# PidiPC.net
KiCad netlist of a schematic drawn in EAGLE
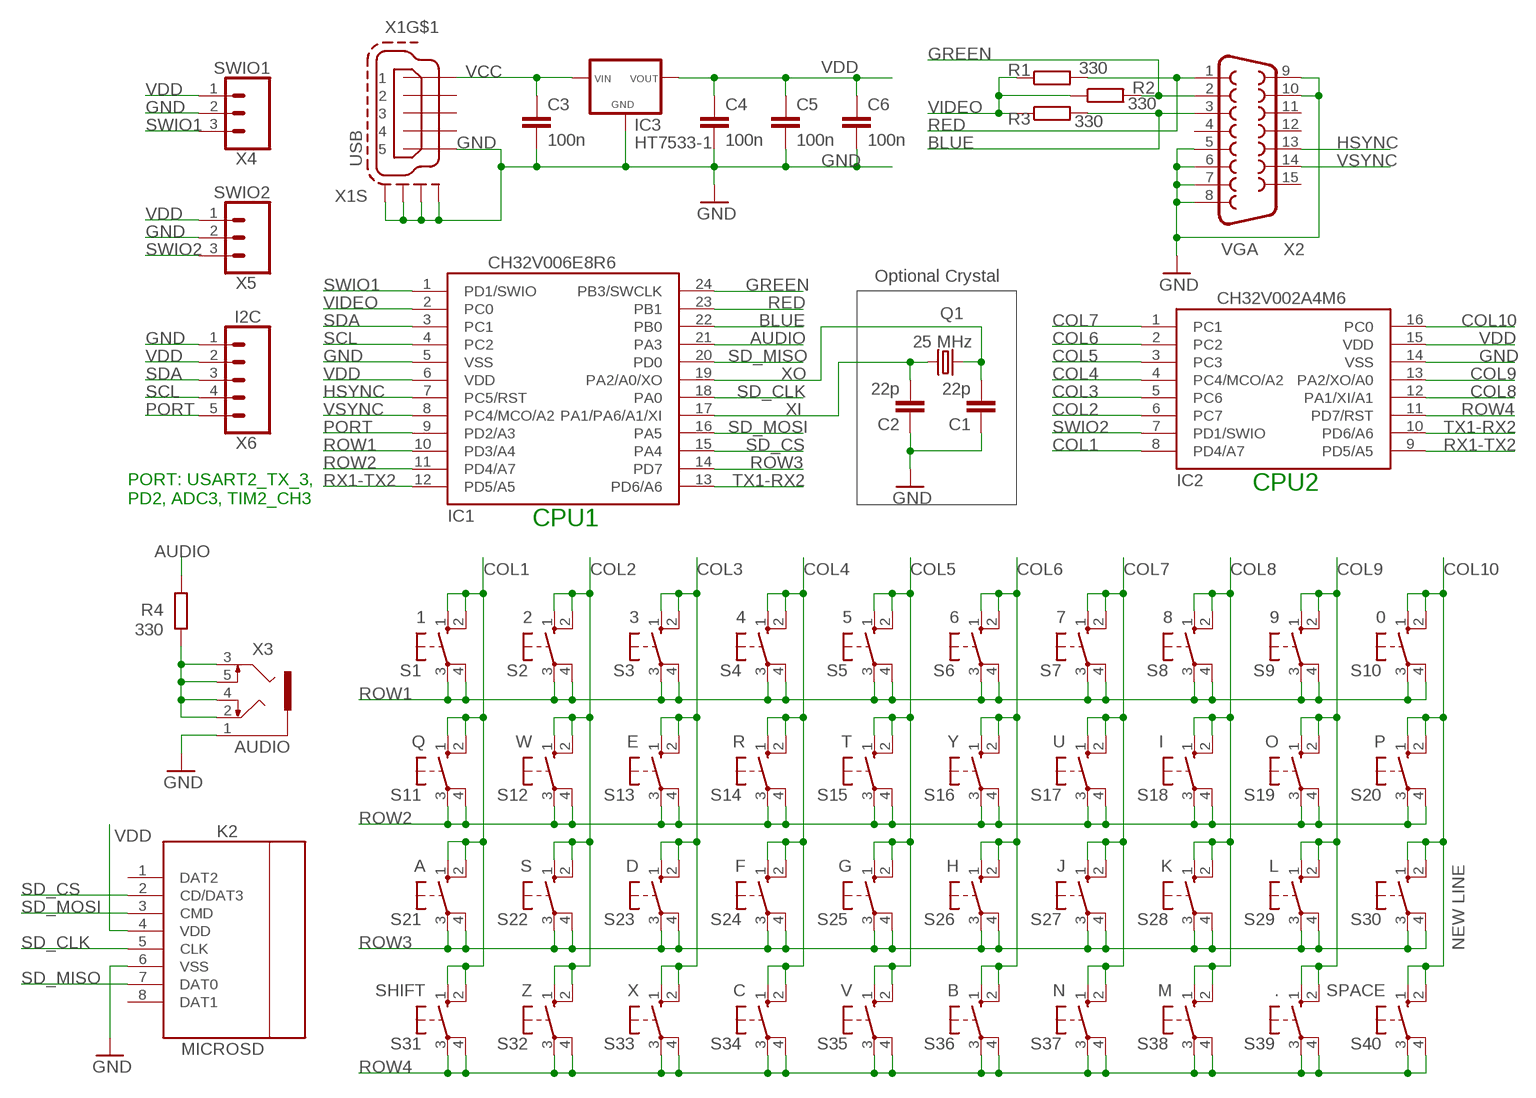
[diagram p0: schematic, sheet 1]

(export (version "E")
  (design (tool "Eeschema 10.0.6"))
  (components
    (comp (ref "C1")
      (value "22p")
      (footprint "eagle-import:C050-024X044")
      (libsource (lib "eagle-import") (part "C-EU050-024X044"))
    )
    (comp (ref "C2")
      (value "22p")
      (footprint "eagle-import:C050-024X044")
      (libsource (lib "eagle-import") (part "C-EU050-024X044"))
    )
    (comp (ref "C3")
      (value "100n")
      (footprint "eagle-import:C050-024X044")
      (libsource (lib "eagle-import") (part "C-EU050-024X044"))
    )
    (comp (ref "C4")
      (value "100n")
      (footprint "eagle-import:C050-024X044")
      (libsource (lib "eagle-import") (part "C-EU050-024X044"))
    )
    (comp (ref "C5")
      (value "100n")
      (footprint "eagle-import:C050-024X044")
      (libsource (lib "eagle-import") (part "C-EU050-024X044"))
    )
    (comp (ref "C6")
      (value "100n")
      (footprint "eagle-import:C050-024X044")
      (libsource (lib "eagle-import") (part "C-EU050-024X044"))
    )
    (comp (ref "IC1")
      (value "CH32V006E8R6")
      (footprint "eagle-import:QSOP24")
      (libsource (lib "eagle-import") (part "CH32V006E8R6"))
    )
    (comp (ref "IC2")
      (value "CH32V002A4M6")
      (footprint "eagle-import:SOP16")
      (libsource (lib "eagle-import") (part "CH32V002A4M6"))
    )
    (comp (ref "IC3")
      (value "HT7533-1")
      (footprint "eagle-import:HT7533-1")
      (libsource (lib "eagle-import") (part "HT7533-1"))
    )
    (comp (ref "K2")
      (value "MICROSD")
      (footprint "eagle-import:MICROSD")
      (libsource (lib "eagle-import") (part "MICROSD"))
    )
    (comp (ref "Q1")
      (value "25 MHz")
      (footprint "eagle-import:HC49U-V")
      (libsource (lib "eagle-import") (part "CRYSTALHC49U-V"))
    )
    (comp (ref "R1")
      (value "330")
      (footprint "eagle-import:0204_7")
      (libsource (lib "eagle-import") (part "R-EU_0204/7"))
    )
    (comp (ref "R2")
      (value "330")
      (footprint "eagle-import:0204_7")
      (libsource (lib "eagle-import") (part "R-EU_0204/7"))
    )
    (comp (ref "R3")
      (value "330")
      (footprint "eagle-import:0204_7")
      (libsource (lib "eagle-import") (part "R-EU_0204/7"))
    )
    (comp (ref "R4")
      (value "330")
      (footprint "eagle-import:0204_7")
      (libsource (lib "eagle-import") (part "R-EU_0204/7"))
    )
    (comp (ref "S1")
      (value "1")
      (footprint "eagle-import:B3F-10XX")
      (fields (field (name "MPN") "B3F-1000"))
      (libsource (lib "eagle-import") (part "10-XX"))
    )
    (comp (ref "S2")
      (value "2")
      (footprint "eagle-import:B3F-10XX")
      (fields (field (name "MPN") "B3F-1000"))
      (libsource (lib "eagle-import") (part "10-XX"))
    )
    (comp (ref "S3")
      (value "3")
      (footprint "eagle-import:B3F-10XX")
      (fields (field (name "MPN") "B3F-1000"))
      (libsource (lib "eagle-import") (part "10-XX"))
    )
    (comp (ref "S4")
      (value "4")
      (footprint "eagle-import:B3F-10XX")
      (fields (field (name "MPN") "B3F-1000"))
      (libsource (lib "eagle-import") (part "10-XX"))
    )
    (comp (ref "S5")
      (value "5")
      (footprint "eagle-import:B3F-10XX")
      (fields (field (name "MPN") "B3F-1000"))
      (libsource (lib "eagle-import") (part "10-XX"))
    )
    (comp (ref "S6")
      (value "6")
      (footprint "eagle-import:B3F-10XX")
      (fields (field (name "MPN") "B3F-1000"))
      (libsource (lib "eagle-import") (part "10-XX"))
    )
    (comp (ref "S7")
      (value "7")
      (footprint "eagle-import:B3F-10XX")
      (fields (field (name "MPN") "B3F-1000"))
      (libsource (lib "eagle-import") (part "10-XX"))
    )
    (comp (ref "S8")
      (value "8")
      (footprint "eagle-import:B3F-10XX")
      (fields (field (name "MPN") "B3F-1000"))
      (libsource (lib "eagle-import") (part "10-XX"))
    )
    (comp (ref "S9")
      (value "9")
      (footprint "eagle-import:B3F-10XX")
      (fields (field (name "MPN") "B3F-1000"))
      (libsource (lib "eagle-import") (part "10-XX"))
    )
    (comp (ref "S10")
      (value "0")
      (footprint "eagle-import:B3F-10XX")
      (fields (field (name "MPN") "B3F-1000"))
      (libsource (lib "eagle-import") (part "10-XX"))
    )
    (comp (ref "S11")
      (value "Q")
      (footprint "eagle-import:B3F-10XX")
      (fields (field (name "MPN") "B3F-1000"))
      (libsource (lib "eagle-import") (part "10-XX"))
    )
    (comp (ref "S12")
      (value "W")
      (footprint "eagle-import:B3F-10XX")
      (fields (field (name "MPN") "B3F-1000"))
      (libsource (lib "eagle-import") (part "10-XX"))
    )
    (comp (ref "S13")
      (value "E")
      (footprint "eagle-import:B3F-10XX")
      (fields (field (name "MPN") "B3F-1000"))
      (libsource (lib "eagle-import") (part "10-XX"))
    )
    (comp (ref "S14")
      (value "R")
      (footprint "eagle-import:B3F-10XX")
      (fields (field (name "MPN") "B3F-1000"))
      (libsource (lib "eagle-import") (part "10-XX"))
    )
    (comp (ref "S15")
      (value "T")
      (footprint "eagle-import:B3F-10XX")
      (fields (field (name "MPN") "B3F-1000"))
      (libsource (lib "eagle-import") (part "10-XX"))
    )
    (comp (ref "S16")
      (value "Y")
      (footprint "eagle-import:B3F-10XX")
      (fields (field (name "MPN") "B3F-1000"))
      (libsource (lib "eagle-import") (part "10-XX"))
    )
    (comp (ref "S17")
      (value "U")
      (footprint "eagle-import:B3F-10XX")
      (fields (field (name "MPN") "B3F-1000"))
      (libsource (lib "eagle-import") (part "10-XX"))
    )
    (comp (ref "S18")
      (value "I")
      (footprint "eagle-import:B3F-10XX")
      (fields (field (name "MPN") "B3F-1000"))
      (libsource (lib "eagle-import") (part "10-XX"))
    )
    (comp (ref "S19")
      (value "O")
      (footprint "eagle-import:B3F-10XX")
      (fields (field (name "MPN") "B3F-1000"))
      (libsource (lib "eagle-import") (part "10-XX"))
    )
    (comp (ref "S20")
      (value "P")
      (footprint "eagle-import:B3F-10XX")
      (fields (field (name "MPN") "B3F-1000"))
      (libsource (lib "eagle-import") (part "10-XX"))
    )
    (comp (ref "S21")
      (value "A")
      (footprint "eagle-import:B3F-10XX")
      (fields (field (name "MPN") "B3F-1000"))
      (libsource (lib "eagle-import") (part "10-XX"))
    )
    (comp (ref "S22")
      (value "S")
      (footprint "eagle-import:B3F-10XX")
      (fields (field (name "MPN") "B3F-1000"))
      (libsource (lib "eagle-import") (part "10-XX"))
    )
    (comp (ref "S23")
      (value "D")
      (footprint "eagle-import:B3F-10XX")
      (fields (field (name "MPN") "B3F-1000"))
      (libsource (lib "eagle-import") (part "10-XX"))
    )
    (comp (ref "S24")
      (value "F")
      (footprint "eagle-import:B3F-10XX")
      (fields (field (name "MPN") "B3F-1000"))
      (libsource (lib "eagle-import") (part "10-XX"))
    )
    (comp (ref "S25")
      (value "G")
      (footprint "eagle-import:B3F-10XX")
      (fields (field (name "MPN") "B3F-1000"))
      (libsource (lib "eagle-import") (part "10-XX"))
    )
    (comp (ref "S26")
      (value "H")
      (footprint "eagle-import:B3F-10XX")
      (fields (field (name "MPN") "B3F-1000"))
      (libsource (lib "eagle-import") (part "10-XX"))
    )
    (comp (ref "S27")
      (value "J")
      (footprint "eagle-import:B3F-10XX")
      (fields (field (name "MPN") "B3F-1000"))
      (libsource (lib "eagle-import") (part "10-XX"))
    )
    (comp (ref "S28")
      (value "K")
      (footprint "eagle-import:B3F-10XX")
      (fields (field (name "MPN") "B3F-1000"))
      (libsource (lib "eagle-import") (part "10-XX"))
    )
    (comp (ref "S29")
      (value "L")
      (footprint "eagle-import:B3F-10XX")
      (fields (field (name "MPN") "B3F-1000"))
      (libsource (lib "eagle-import") (part "10-XX"))
    )
    (comp (ref "S30")
      (value "NEW LINE")
      (footprint "eagle-import:B3F-10XX")
      (fields (field (name "MPN") "B3F-1000"))
      (libsource (lib "eagle-import") (part "10-XX"))
    )
    (comp (ref "S31")
      (value "SHIFT")
      (footprint "eagle-import:B3F-10XX")
      (fields (field (name "MPN") "B3F-1000"))
      (libsource (lib "eagle-import") (part "10-XX"))
    )
    (comp (ref "S32")
      (value "Z")
      (footprint "eagle-import:B3F-10XX")
      (fields (field (name "MPN") "B3F-1000"))
      (libsource (lib "eagle-import") (part "10-XX"))
    )
    (comp (ref "S33")
      (value "X")
      (footprint "eagle-import:B3F-10XX")
      (fields (field (name "MPN") "B3F-1000"))
      (libsource (lib "eagle-import") (part "10-XX"))
    )
    (comp (ref "S34")
      (value "C")
      (footprint "eagle-import:B3F-10XX")
      (fields (field (name "MPN") "B3F-1000"))
      (libsource (lib "eagle-import") (part "10-XX"))
    )
    (comp (ref "S35")
      (value "V")
      (footprint "eagle-import:B3F-10XX")
      (fields (field (name "MPN") "B3F-1000"))
      (libsource (lib "eagle-import") (part "10-XX"))
    )
    (comp (ref "S36")
      (value "B")
      (footprint "eagle-import:B3F-10XX")
      (fields (field (name "MPN") "B3F-1000"))
      (libsource (lib "eagle-import") (part "10-XX"))
    )
    (comp (ref "S37")
      (value "N")
      (footprint "eagle-import:B3F-10XX")
      (fields (field (name "MPN") "B3F-1000"))
      (libsource (lib "eagle-import") (part "10-XX"))
    )
    (comp (ref "S38")
      (value "M")
      (footprint "eagle-import:B3F-10XX")
      (fields (field (name "MPN") "B3F-1000"))
      (libsource (lib "eagle-import") (part "10-XX"))
    )
    (comp (ref "S39")
      (value ".")
      (footprint "eagle-import:B3F-10XX")
      (fields (field (name "MPN") "B3F-1000"))
      (libsource (lib "eagle-import") (part "10-XX"))
    )
    (comp (ref "S40")
      (value "SPACE")
      (footprint "eagle-import:B3F-10XX")
      (fields (field (name "MPN") "B3F-1000"))
      (libsource (lib "eagle-import") (part "10-XX"))
    )
    (comp (ref "X1")
      (value "USB")
      (footprint "eagle-import:32005-201")
      (libsource (lib "eagle-import") (part "MINI-USB-SCHIELD-32005-201"))
    )
    (comp (ref "X2")
      (value "VGA")
      (footprint "eagle-import:HDF15H")
      (libsource (lib "eagle-import") (part "F15HDH"))
    )
    (comp (ref "X3")
      (value "AUDIO")
      (footprint "eagle-import:1503_09")
      (libsource (lib "eagle-import") (part "1503_09"))
    )
    (comp (ref "X4")
      (value "SWIO1")
      (footprint "eagle-import:1X03_LONGPADS")
      (libsource (lib "eagle-import") (part "CONN_03LONGPADS"))
    )
    (comp (ref "X5")
      (value "SWIO2")
      (footprint "eagle-import:1X03_LONGPADS")
      (libsource (lib "eagle-import") (part "CONN_03LONGPADS"))
    )
    (comp (ref "X6")
      (value "I2C")
      (footprint "eagle-import:1X05_LONGPADS")
      (libsource (lib "eagle-import") (part "CONN_05PTH_LONGPADS"))
    )
  )
  (nets
    (net (code "1") (name "/AUDIO") (class "Default")
      (node (ref "IC1") (pin "21") (pinfunction "PA3_21") (pintype "bidirectional"))
      (node (ref "R4") (pin "2") (pinfunction "2_2") (pintype "passive"))
    )
    (net (code "2") (name "/BLUE") (class "Default")
      (node (ref "IC1") (pin "22") (pinfunction "PB0_22") (pintype "bidirectional"))
      (node (ref "R3") (pin "2") (pinfunction "2_2") (pintype "passive"))
      (node (ref "X2") (pin "3") (pinfunction "3_3") (pintype "passive"))
    )
    (net (code "3") (name "/COL1") (class "Default")
      (node (ref "IC2") (pin "8") (pinfunction "PD4/A7_8") (pintype "bidirectional"))
      (node (ref "S1") (pin "1") (pinfunction "S_1") (pintype "passive"))
      (node (ref "S1") (pin "2") (pinfunction "S1_2") (pintype "passive"))
      (node (ref "S11") (pin "1") (pinfunction "S_1") (pintype "passive"))
      (node (ref "S11") (pin "2") (pinfunction "S1_2") (pintype "passive"))
      (node (ref "S21") (pin "1") (pinfunction "S_1") (pintype "passive"))
      (node (ref "S21") (pin "2") (pinfunction "S1_2") (pintype "passive"))
      (node (ref "S31") (pin "1") (pinfunction "S_1") (pintype "passive"))
      (node (ref "S31") (pin "2") (pinfunction "S1_2") (pintype "passive"))
    )
    (net (code "4") (name "/COL2") (class "Default")
      (node (ref "IC2") (pin "6") (pinfunction "PC7_6") (pintype "bidirectional"))
      (node (ref "S12") (pin "1") (pinfunction "S_1") (pintype "passive"))
      (node (ref "S12") (pin "2") (pinfunction "S1_2") (pintype "passive"))
      (node (ref "S2") (pin "1") (pinfunction "S_1") (pintype "passive"))
      (node (ref "S2") (pin "2") (pinfunction "S1_2") (pintype "passive"))
      (node (ref "S22") (pin "1") (pinfunction "S_1") (pintype "passive"))
      (node (ref "S22") (pin "2") (pinfunction "S1_2") (pintype "passive"))
      (node (ref "S32") (pin "1") (pinfunction "S_1") (pintype "passive"))
      (node (ref "S32") (pin "2") (pinfunction "S1_2") (pintype "passive"))
    )
    (net (code "5") (name "/COL3") (class "Default")
      (node (ref "IC2") (pin "5") (pinfunction "PC6_5") (pintype "bidirectional"))
      (node (ref "S13") (pin "1") (pinfunction "S_1") (pintype "passive"))
      (node (ref "S13") (pin "2") (pinfunction "S1_2") (pintype "passive"))
      (node (ref "S23") (pin "1") (pinfunction "S_1") (pintype "passive"))
      (node (ref "S23") (pin "2") (pinfunction "S1_2") (pintype "passive"))
      (node (ref "S3") (pin "1") (pinfunction "S_1") (pintype "passive"))
      (node (ref "S3") (pin "2") (pinfunction "S1_2") (pintype "passive"))
      (node (ref "S33") (pin "1") (pinfunction "S_1") (pintype "passive"))
      (node (ref "S33") (pin "2") (pinfunction "S1_2") (pintype "passive"))
    )
    (net (code "6") (name "/COL4") (class "Default")
      (node (ref "IC2") (pin "4") (pinfunction "PC4/MCO/A2_4") (pintype "bidirectional"))
      (node (ref "S14") (pin "1") (pinfunction "S_1") (pintype "passive"))
      (node (ref "S14") (pin "2") (pinfunction "S1_2") (pintype "passive"))
      (node (ref "S24") (pin "1") (pinfunction "S_1") (pintype "passive"))
      (node (ref "S24") (pin "2") (pinfunction "S1_2") (pintype "passive"))
      (node (ref "S34") (pin "1") (pinfunction "S_1") (pintype "passive"))
      (node (ref "S34") (pin "2") (pinfunction "S1_2") (pintype "passive"))
      (node (ref "S4") (pin "1") (pinfunction "S_1") (pintype "passive"))
      (node (ref "S4") (pin "2") (pinfunction "S1_2") (pintype "passive"))
    )
    (net (code "7") (name "/COL5") (class "Default")
      (node (ref "IC2") (pin "3") (pinfunction "PC3_3") (pintype "bidirectional"))
      (node (ref "S15") (pin "1") (pinfunction "S_1") (pintype "passive"))
      (node (ref "S15") (pin "2") (pinfunction "S1_2") (pintype "passive"))
      (node (ref "S25") (pin "1") (pinfunction "S_1") (pintype "passive"))
      (node (ref "S25") (pin "2") (pinfunction "S1_2") (pintype "passive"))
      (node (ref "S35") (pin "1") (pinfunction "S_1") (pintype "passive"))
      (node (ref "S35") (pin "2") (pinfunction "S1_2") (pintype "passive"))
      (node (ref "S5") (pin "1") (pinfunction "S_1") (pintype "passive"))
      (node (ref "S5") (pin "2") (pinfunction "S1_2") (pintype "passive"))
    )
    (net (code "8") (name "/COL6") (class "Default")
      (node (ref "IC2") (pin "2") (pinfunction "PC2_2") (pintype "bidirectional"))
      (node (ref "S16") (pin "1") (pinfunction "S_1") (pintype "passive"))
      (node (ref "S16") (pin "2") (pinfunction "S1_2") (pintype "passive"))
      (node (ref "S26") (pin "1") (pinfunction "S_1") (pintype "passive"))
      (node (ref "S26") (pin "2") (pinfunction "S1_2") (pintype "passive"))
      (node (ref "S36") (pin "1") (pinfunction "S_1") (pintype "passive"))
      (node (ref "S36") (pin "2") (pinfunction "S1_2") (pintype "passive"))
      (node (ref "S6") (pin "1") (pinfunction "S_1") (pintype "passive"))
      (node (ref "S6") (pin "2") (pinfunction "S1_2") (pintype "passive"))
    )
    (net (code "9") (name "/COL7") (class "Default")
      (node (ref "IC2") (pin "1") (pinfunction "PC1_1") (pintype "bidirectional"))
      (node (ref "S17") (pin "1") (pinfunction "S_1") (pintype "passive"))
      (node (ref "S17") (pin "2") (pinfunction "S1_2") (pintype "passive"))
      (node (ref "S27") (pin "1") (pinfunction "S_1") (pintype "passive"))
      (node (ref "S27") (pin "2") (pinfunction "S1_2") (pintype "passive"))
      (node (ref "S37") (pin "1") (pinfunction "S_1") (pintype "passive"))
      (node (ref "S37") (pin "2") (pinfunction "S1_2") (pintype "passive"))
      (node (ref "S7") (pin "1") (pinfunction "S_1") (pintype "passive"))
      (node (ref "S7") (pin "2") (pinfunction "S1_2") (pintype "passive"))
    )
    (net (code "10") (name "/COL8") (class "Default")
      (node (ref "IC2") (pin "12") (pinfunction "PA1/XI/A1_12") (pintype "bidirectional"))
      (node (ref "S18") (pin "1") (pinfunction "S_1") (pintype "passive"))
      (node (ref "S18") (pin "2") (pinfunction "S1_2") (pintype "passive"))
      (node (ref "S28") (pin "1") (pinfunction "S_1") (pintype "passive"))
      (node (ref "S28") (pin "2") (pinfunction "S1_2") (pintype "passive"))
      (node (ref "S38") (pin "1") (pinfunction "S_1") (pintype "passive"))
      (node (ref "S38") (pin "2") (pinfunction "S1_2") (pintype "passive"))
      (node (ref "S8") (pin "1") (pinfunction "S_1") (pintype "passive"))
      (node (ref "S8") (pin "2") (pinfunction "S1_2") (pintype "passive"))
    )
    (net (code "11") (name "/COL9") (class "Default")
      (node (ref "IC2") (pin "13") (pinfunction "PA2/XO/A0_13") (pintype "bidirectional"))
      (node (ref "S19") (pin "1") (pinfunction "S_1") (pintype "passive"))
      (node (ref "S19") (pin "2") (pinfunction "S1_2") (pintype "passive"))
      (node (ref "S29") (pin "1") (pinfunction "S_1") (pintype "passive"))
      (node (ref "S29") (pin "2") (pinfunction "S1_2") (pintype "passive"))
      (node (ref "S39") (pin "1") (pinfunction "S_1") (pintype "passive"))
      (node (ref "S39") (pin "2") (pinfunction "S1_2") (pintype "passive"))
      (node (ref "S9") (pin "1") (pinfunction "S_1") (pintype "passive"))
      (node (ref "S9") (pin "2") (pinfunction "S1_2") (pintype "passive"))
    )
    (net (code "12") (name "/COL10") (class "Default")
      (node (ref "IC2") (pin "16") (pinfunction "PC0_16") (pintype "bidirectional"))
      (node (ref "S10") (pin "1") (pinfunction "S_1") (pintype "passive"))
      (node (ref "S10") (pin "2") (pinfunction "S1_2") (pintype "passive"))
      (node (ref "S20") (pin "1") (pinfunction "S_1") (pintype "passive"))
      (node (ref "S20") (pin "2") (pinfunction "S1_2") (pintype "passive"))
      (node (ref "S30") (pin "1") (pinfunction "S_1") (pintype "passive"))
      (node (ref "S30") (pin "2") (pinfunction "S1_2") (pintype "passive"))
      (node (ref "S40") (pin "1") (pinfunction "S_1") (pintype "passive"))
      (node (ref "S40") (pin "2") (pinfunction "S1_2") (pintype "passive"))
    )
    (net (code "13") (name "/GREEN") (class "Default")
      (node (ref "IC1") (pin "24") (pinfunction "PB3/SWCLK_24") (pintype "bidirectional"))
      (node (ref "R2") (pin "2") (pinfunction "2_2") (pintype "passive"))
      (node (ref "X2") (pin "2") (pinfunction "2_2") (pintype "passive"))
    )
    (net (code "14") (name "/HSYNC") (class "Default")
      (node (ref "IC1") (pin "7") (pinfunction "PC5/RST_7") (pintype "bidirectional"))
      (node (ref "X2") (pin "13") (pinfunction "13_13") (pintype "passive"))
    )
    (net (code "15") (name "/PORT") (class "Default")
      (node (ref "IC1") (pin "9") (pinfunction "PD2/A3_9") (pintype "bidirectional"))
      (node (ref "X6") (pin "5") (pinfunction "5_5") (pintype "passive"))
    )
    (net (code "16") (name "/RED") (class "Default")
      (node (ref "IC1") (pin "23") (pinfunction "PB1_23") (pintype "bidirectional"))
      (node (ref "R1") (pin "2") (pinfunction "2_2") (pintype "passive"))
      (node (ref "X2") (pin "1") (pinfunction "1_1") (pintype "passive"))
    )
    (net (code "17") (name "/ROW1") (class "Default")
      (node (ref "IC1") (pin "10") (pinfunction "PD3/A4_10") (pintype "bidirectional"))
      (node (ref "S1") (pin "3") (pinfunction "P_3") (pintype "passive"))
      (node (ref "S1") (pin "4") (pinfunction "P1_4") (pintype "passive"))
      (node (ref "S10") (pin "3") (pinfunction "P_3") (pintype "passive"))
      (node (ref "S10") (pin "4") (pinfunction "P1_4") (pintype "passive"))
      (node (ref "S2") (pin "3") (pinfunction "P_3") (pintype "passive"))
      (node (ref "S2") (pin "4") (pinfunction "P1_4") (pintype "passive"))
      (node (ref "S3") (pin "3") (pinfunction "P_3") (pintype "passive"))
      (node (ref "S3") (pin "4") (pinfunction "P1_4") (pintype "passive"))
      (node (ref "S4") (pin "3") (pinfunction "P_3") (pintype "passive"))
      (node (ref "S4") (pin "4") (pinfunction "P1_4") (pintype "passive"))
      (node (ref "S5") (pin "3") (pinfunction "P_3") (pintype "passive"))
      (node (ref "S5") (pin "4") (pinfunction "P1_4") (pintype "passive"))
      (node (ref "S6") (pin "3") (pinfunction "P_3") (pintype "passive"))
      (node (ref "S6") (pin "4") (pinfunction "P1_4") (pintype "passive"))
      (node (ref "S7") (pin "3") (pinfunction "P_3") (pintype "passive"))
      (node (ref "S7") (pin "4") (pinfunction "P1_4") (pintype "passive"))
      (node (ref "S8") (pin "3") (pinfunction "P_3") (pintype "passive"))
      (node (ref "S8") (pin "4") (pinfunction "P1_4") (pintype "passive"))
      (node (ref "S9") (pin "3") (pinfunction "P_3") (pintype "passive"))
      (node (ref "S9") (pin "4") (pinfunction "P1_4") (pintype "passive"))
    )
    (net (code "18") (name "/ROW2") (class "Default")
      (node (ref "IC1") (pin "11") (pinfunction "PD4/A7_11") (pintype "bidirectional"))
      (node (ref "S11") (pin "3") (pinfunction "P_3") (pintype "passive"))
      (node (ref "S11") (pin "4") (pinfunction "P1_4") (pintype "passive"))
      (node (ref "S12") (pin "3") (pinfunction "P_3") (pintype "passive"))
      (node (ref "S12") (pin "4") (pinfunction "P1_4") (pintype "passive"))
      (node (ref "S13") (pin "3") (pinfunction "P_3") (pintype "passive"))
      (node (ref "S13") (pin "4") (pinfunction "P1_4") (pintype "passive"))
      (node (ref "S14") (pin "3") (pinfunction "P_3") (pintype "passive"))
      (node (ref "S14") (pin "4") (pinfunction "P1_4") (pintype "passive"))
      (node (ref "S15") (pin "3") (pinfunction "P_3") (pintype "passive"))
      (node (ref "S15") (pin "4") (pinfunction "P1_4") (pintype "passive"))
      (node (ref "S16") (pin "3") (pinfunction "P_3") (pintype "passive"))
      (node (ref "S16") (pin "4") (pinfunction "P1_4") (pintype "passive"))
      (node (ref "S17") (pin "3") (pinfunction "P_3") (pintype "passive"))
      (node (ref "S17") (pin "4") (pinfunction "P1_4") (pintype "passive"))
      (node (ref "S18") (pin "3") (pinfunction "P_3") (pintype "passive"))
      (node (ref "S18") (pin "4") (pinfunction "P1_4") (pintype "passive"))
      (node (ref "S19") (pin "3") (pinfunction "P_3") (pintype "passive"))
      (node (ref "S19") (pin "4") (pinfunction "P1_4") (pintype "passive"))
      (node (ref "S20") (pin "3") (pinfunction "P_3") (pintype "passive"))
      (node (ref "S20") (pin "4") (pinfunction "P1_4") (pintype "passive"))
    )
    (net (code "19") (name "/ROW3") (class "Default")
      (node (ref "IC1") (pin "14") (pinfunction "PD7_14") (pintype "bidirectional"))
      (node (ref "S21") (pin "3") (pinfunction "P_3") (pintype "passive"))
      (node (ref "S21") (pin "4") (pinfunction "P1_4") (pintype "passive"))
      (node (ref "S22") (pin "3") (pinfunction "P_3") (pintype "passive"))
      (node (ref "S22") (pin "4") (pinfunction "P1_4") (pintype "passive"))
      (node (ref "S23") (pin "3") (pinfunction "P_3") (pintype "passive"))
      (node (ref "S23") (pin "4") (pinfunction "P1_4") (pintype "passive"))
      (node (ref "S24") (pin "3") (pinfunction "P_3") (pintype "passive"))
      (node (ref "S24") (pin "4") (pinfunction "P1_4") (pintype "passive"))
      (node (ref "S25") (pin "3") (pinfunction "P_3") (pintype "passive"))
      (node (ref "S25") (pin "4") (pinfunction "P1_4") (pintype "passive"))
      (node (ref "S26") (pin "3") (pinfunction "P_3") (pintype "passive"))
      (node (ref "S26") (pin "4") (pinfunction "P1_4") (pintype "passive"))
      (node (ref "S27") (pin "3") (pinfunction "P_3") (pintype "passive"))
      (node (ref "S27") (pin "4") (pinfunction "P1_4") (pintype "passive"))
      (node (ref "S28") (pin "3") (pinfunction "P_3") (pintype "passive"))
      (node (ref "S28") (pin "4") (pinfunction "P1_4") (pintype "passive"))
      (node (ref "S29") (pin "3") (pinfunction "P_3") (pintype "passive"))
      (node (ref "S29") (pin "4") (pinfunction "P1_4") (pintype "passive"))
      (node (ref "S30") (pin "3") (pinfunction "P_3") (pintype "passive"))
      (node (ref "S30") (pin "4") (pinfunction "P1_4") (pintype "passive"))
    )
    (net (code "20") (name "/ROW4") (class "Default")
      (node (ref "IC2") (pin "11") (pinfunction "PD7/RST_11") (pintype "bidirectional"))
      (node (ref "S31") (pin "3") (pinfunction "P_3") (pintype "passive"))
      (node (ref "S31") (pin "4") (pinfunction "P1_4") (pintype "passive"))
      (node (ref "S32") (pin "3") (pinfunction "P_3") (pintype "passive"))
      (node (ref "S32") (pin "4") (pinfunction "P1_4") (pintype "passive"))
      (node (ref "S33") (pin "3") (pinfunction "P_3") (pintype "passive"))
      (node (ref "S33") (pin "4") (pinfunction "P1_4") (pintype "passive"))
      (node (ref "S34") (pin "3") (pinfunction "P_3") (pintype "passive"))
      (node (ref "S34") (pin "4") (pinfunction "P1_4") (pintype "passive"))
      (node (ref "S35") (pin "3") (pinfunction "P_3") (pintype "passive"))
      (node (ref "S35") (pin "4") (pinfunction "P1_4") (pintype "passive"))
      (node (ref "S36") (pin "3") (pinfunction "P_3") (pintype "passive"))
      (node (ref "S36") (pin "4") (pinfunction "P1_4") (pintype "passive"))
      (node (ref "S37") (pin "3") (pinfunction "P_3") (pintype "passive"))
      (node (ref "S37") (pin "4") (pinfunction "P1_4") (pintype "passive"))
      (node (ref "S38") (pin "3") (pinfunction "P_3") (pintype "passive"))
      (node (ref "S38") (pin "4") (pinfunction "P1_4") (pintype "passive"))
      (node (ref "S39") (pin "3") (pinfunction "P_3") (pintype "passive"))
      (node (ref "S39") (pin "4") (pinfunction "P1_4") (pintype "passive"))
      (node (ref "S40") (pin "3") (pinfunction "P_3") (pintype "passive"))
      (node (ref "S40") (pin "4") (pinfunction "P1_4") (pintype "passive"))
    )
    (net (code "21") (name "/RX1-TX2") (class "Default")
      (node (ref "IC1") (pin "12") (pinfunction "PD5/A5_12") (pintype "bidirectional"))
      (node (ref "IC2") (pin "9") (pinfunction "PD5/A5_9") (pintype "bidirectional"))
    )
    (net (code "22") (name "/SCL") (class "Default")
      (node (ref "IC1") (pin "4") (pinfunction "PC2_4") (pintype "bidirectional"))
      (node (ref "X6") (pin "4") (pinfunction "4_4") (pintype "passive"))
    )
    (net (code "23") (name "/SDA") (class "Default")
      (node (ref "IC1") (pin "3") (pinfunction "PC1_3") (pintype "bidirectional"))
      (node (ref "X6") (pin "3") (pinfunction "3_3") (pintype "passive"))
    )
    (net (code "24") (name "/SD_CLK") (class "Default")
      (node (ref "IC1") (pin "18") (pinfunction "PA0_18") (pintype "bidirectional"))
      (node (ref "K2") (pin "5") (pinfunction "CLK_5") (pintype "bidirectional"))
    )
    (net (code "25") (name "/SD_CS") (class "Default")
      (node (ref "IC1") (pin "15") (pinfunction "PA4_15") (pintype "bidirectional"))
      (node (ref "K2") (pin "2") (pinfunction "CD/DAT3_2") (pintype "bidirectional"))
    )
    (net (code "26") (name "/SD_MISO") (class "Default")
      (node (ref "IC1") (pin "20") (pinfunction "PD0_20") (pintype "bidirectional"))
      (node (ref "K2") (pin "7") (pinfunction "DAT0_7") (pintype "bidirectional"))
    )
    (net (code "27") (name "/SD_MOSI") (class "Default")
      (node (ref "IC1") (pin "16") (pinfunction "PA5_16") (pintype "bidirectional"))
      (node (ref "K2") (pin "3") (pinfunction "CMD_3") (pintype "bidirectional"))
    )
    (net (code "28") (name "/SWIO1") (class "Default")
      (node (ref "IC1") (pin "1") (pinfunction "PD1/SWIO_1") (pintype "bidirectional"))
      (node (ref "X4") (pin "3") (pinfunction "3_3") (pintype "passive"))
    )
    (net (code "29") (name "/SWIO2") (class "Default")
      (node (ref "IC2") (pin "7") (pinfunction "PD1/SWIO_7") (pintype "bidirectional"))
      (node (ref "X5") (pin "3") (pinfunction "3_3") (pintype "passive"))
    )
    (net (code "30") (name "/TX1-RX2") (class "Default")
      (node (ref "IC1") (pin "13") (pinfunction "PD6/A6_13") (pintype "bidirectional"))
      (node (ref "IC2") (pin "10") (pinfunction "PD6/A6_10") (pintype "bidirectional"))
    )
    (net (code "31") (name "/VCC") (class "Default")
      (node (ref "C3") (pin "1") (pinfunction "1_1") (pintype "passive"))
      (node (ref "IC3") (pin "VIN") (pinfunction "VIN_VIN") (pintype "input"))
      (node (ref "X1") (pin "1") (pinfunction "1_1") (pintype "passive"))
    )
    (net (code "32") (name "/VDD") (class "Default")
      (node (ref "C4") (pin "1") (pinfunction "1_1") (pintype "passive"))
      (node (ref "C5") (pin "1") (pinfunction "1_1") (pintype "passive"))
      (node (ref "C6") (pin "1") (pinfunction "1_1") (pintype "passive"))
      (node (ref "IC1") (pin "6") (pinfunction "VDD_6") (pintype "power_in"))
      (node (ref "IC2") (pin "15") (pinfunction "VDD_15") (pintype "power_in"))
      (node (ref "IC3") (pin "VOUT") (pinfunction "VOUT_VOUT") (pintype "passive"))
      (node (ref "K2") (pin "4") (pinfunction "VDD_4") (pintype "bidirectional"))
      (node (ref "X4") (pin "1") (pinfunction "1_1") (pintype "passive"))
      (node (ref "X5") (pin "1") (pinfunction "1_1") (pintype "passive"))
      (node (ref "X6") (pin "2") (pinfunction "2_2") (pintype "passive"))
    )
    (net (code "33") (name "/VIDEO") (class "Default")
      (node (ref "IC1") (pin "2") (pinfunction "PC0_2") (pintype "bidirectional"))
      (node (ref "R1") (pin "1") (pinfunction "1_1") (pintype "passive"))
      (node (ref "R2") (pin "1") (pinfunction "1_1") (pintype "passive"))
      (node (ref "R3") (pin "1") (pinfunction "1_1") (pintype "passive"))
    )
    (net (code "34") (name "/VSYNC") (class "Default")
      (node (ref "IC1") (pin "8") (pinfunction "PC4/MCO/A2_8") (pintype "bidirectional"))
      (node (ref "X2") (pin "14") (pinfunction "14_14") (pintype "passive"))
    )
    (net (code "35") (name "/XI") (class "Default")
      (node (ref "C2") (pin "2") (pinfunction "2_2") (pintype "passive"))
      (node (ref "IC1") (pin "17") (pinfunction "PA1/PA6/A1/XI_17") (pintype "bidirectional"))
      (node (ref "Q1") (pin "2") (pinfunction "2_2") (pintype "passive"))
    )
    (net (code "36") (name "/XO") (class "Default")
      (node (ref "C1") (pin "2") (pinfunction "2_2") (pintype "passive"))
      (node (ref "IC1") (pin "19") (pinfunction "PA2/A0/XO_19") (pintype "bidirectional"))
      (node (ref "Q1") (pin "1") (pinfunction "1_1") (pintype "passive"))
    )
    (net (code "37") (name "GND") (class "Default")
      (node (ref "C1") (pin "1") (pinfunction "1_1") (pintype "passive"))
      (node (ref "C2") (pin "1") (pinfunction "1_1") (pintype "passive"))
      (node (ref "C3") (pin "2") (pinfunction "2_2") (pintype "passive"))
      (node (ref "C4") (pin "2") (pinfunction "2_2") (pintype "passive"))
      (node (ref "C5") (pin "2") (pinfunction "2_2") (pintype "passive"))
      (node (ref "C6") (pin "2") (pinfunction "2_2") (pintype "passive"))
      (node (ref "IC1") (pin "5") (pinfunction "VSS_5") (pintype "power_in"))
      (node (ref "IC2") (pin "14") (pinfunction "VSS_14") (pintype "power_in"))
      (node (ref "IC3") (pin "GND") (pinfunction "GND_GND") (pintype "input"))
      (node (ref "K2") (pin "6") (pinfunction "VSS_6") (pintype "bidirectional"))
      (node (ref "X1") (pin "5") (pinfunction "5_5") (pintype "passive"))
      (node (ref "X1") (pin "M1") (pinfunction "S1_M1") (pintype "passive"))
      (node (ref "X1") (pin "M2") (pinfunction "S2_M2") (pintype "passive"))
      (node (ref "X1") (pin "M3") (pinfunction "S3_M3") (pintype "passive"))
      (node (ref "X1") (pin "M4") (pinfunction "S4_M4") (pintype "passive"))
      (node (ref "X2") (pin "10") (pinfunction "10_10") (pintype "passive"))
      (node (ref "X2") (pin "5") (pinfunction "5_5") (pintype "passive"))
      (node (ref "X2") (pin "6") (pinfunction "6_6") (pintype "passive"))
      (node (ref "X2") (pin "7") (pinfunction "7_7") (pintype "passive"))
      (node (ref "X2") (pin "8") (pinfunction "8_8") (pintype "passive"))
      (node (ref "X2") (pin "9") (pinfunction "9_9") (pintype "passive"))
      (node (ref "X3") (pin "1") (pinfunction "1_1") (pintype "passive"))
      (node (ref "X4") (pin "2") (pinfunction "2_2") (pintype "passive"))
      (node (ref "X5") (pin "2") (pinfunction "2_2") (pintype "passive"))
      (node (ref "X6") (pin "1") (pinfunction "1_1") (pintype "passive"))
    )
    (net (code "38") (name "Net-(R4-Pad1)") (class "Default")
      (node (ref "R4") (pin "1") (pinfunction "1_1") (pintype "passive"))
      (node (ref "X3") (pin "2") (pinfunction "2_2") (pintype "passive"))
      (node (ref "X3") (pin "3") (pinfunction "3_3") (pintype "passive"))
      (node (ref "X3") (pin "4") (pinfunction "4_4") (pintype "passive"))
      (node (ref "X3") (pin "5") (pinfunction "5_5") (pintype "passive"))
    )
    (net (code "39") (name "unconnected-(K2-DAT1-Pad8)") (class "Default")
      (node (ref "K2") (pin "8") (pinfunction "DAT1_8") (pintype "bidirectional"))
    )
    (net (code "40") (name "unconnected-(K2-DAT2-Pad1)") (class "Default")
      (node (ref "K2") (pin "1") (pinfunction "DAT2_1") (pintype "bidirectional"))
    )
    (net (code "41") (name "unconnected-(X1-Pad2)") (class "Default")
      (node (ref "X1") (pin "2") (pinfunction "2_2") (pintype "passive"))
    )
    (net (code "42") (name "unconnected-(X1-Pad3)") (class "Default")
      (node (ref "X1") (pin "3") (pinfunction "3_3") (pintype "passive"))
    )
    (net (code "43") (name "unconnected-(X1-Pad4)") (class "Default")
      (node (ref "X1") (pin "4") (pinfunction "4_4") (pintype "passive"))
    )
    (net (code "44") (name "unconnected-(X2-Pad4)") (class "Default")
      (node (ref "X2") (pin "4") (pinfunction "4_4") (pintype "passive"))
    )
    (net (code "45") (name "unconnected-(X2-Pad11)") (class "Default")
      (node (ref "X2") (pin "11") (pinfunction "11_11") (pintype "passive"))
    )
    (net (code "46") (name "unconnected-(X2-Pad12)") (class "Default")
      (node (ref "X2") (pin "12") (pinfunction "12_12") (pintype "passive"))
    )
    (net (code "47") (name "unconnected-(X2-Pad15)") (class "Default")
      (node (ref "X2") (pin "15") (pinfunction "15_15") (pintype "passive"))
    )
  )
)
